# Connectors.net
KiCad netlist of a schematic drawn in Altium Designer
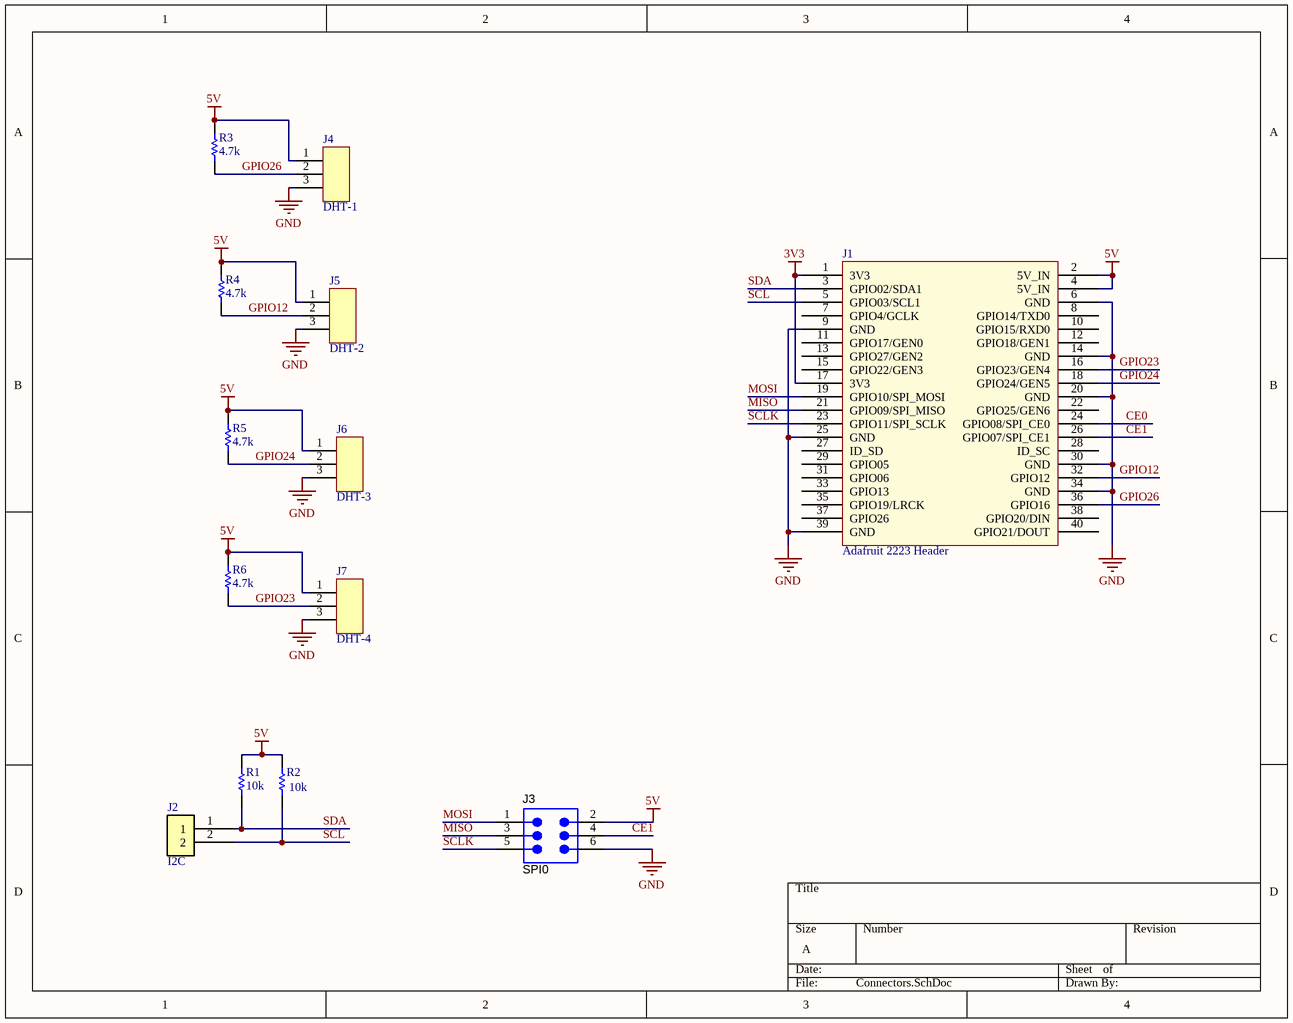
[diagram p0: Connectors.SchDoc]

(export (version "E")
  (design (tool "Eeschema 10.0.6"))
  (components
    (comp (ref "J1")
      (value "Adafruit 2223 Header")
      (footprint "PCB-dv9vmhrfa2chsb9gidwm-1")
      (description "GPIO Stacking Header for Pi A+/B+/Pi 2/Pi 3 - Extra-long 2x20 Pins")
      (libsource (lib "CommunityVault") (part "SYM-cbcb01f7cb9b140c-1"))
    )
    (comp (ref "J2")
      (value "I2C")
      (footprint "PCB-t2j72m1yraok0w090vy8-1")
      (description "Board-To-Board Connector, Right Angle, WR-PHD Series, Through Hole, Header, 2, 2.54 mm")
      (fields (field (name "MANUFACTURER PART NUMBER") "61300211021"))
      (libsource (lib "CommunityVault") (part "SYM-7939b1c60980a6fe-1"))
    )
    (comp (ref "J3")
      (value "SPI0")
      (footprint "PCB-195qa83xwzmdfln5hnix-1")
      (description "Board-To-Board Connector, WR-PHD Series, Surface Mount, Header, 6, 2.54 mm, Gold Plated Contacts")
      (fields (field (name "MANUFACTURER PART NUMBER") "61000621121"))
      (libsource (lib "CommunityVault") (part "Header_3x2"))
    )
    (comp (ref "J4")
      (value "DHT-1")
      (footprint "PCB-s0hfil65plaomi4ibvcw-1")
      (description "THT Vertical Pin Header WR-PHD, Pitch 2.54 mm, Single Row, 3 pins")
      (fields (field (name "MANUFACTURER PART NUMBER") "61300311121"))
      (libsource (lib "CommunityVault") (part "SYM-8a90426ffa175557-17"))
    )
    (comp (ref "J5")
      (value "DHT-2")
      (footprint "PCB-s0hfil65plaomi4ibvcw-1")
      (description "THT Vertical Pin Header WR-PHD, Pitch 2.54 mm, Single Row, 3 pins")
      (fields (field (name "MANUFACTURER PART NUMBER") "61300311121"))
      (libsource (lib "CommunityVault") (part "SYM-8a90426ffa175557-17"))
    )
    (comp (ref "J6")
      (value "DHT-3")
      (footprint "PCB-s0hfil65plaomi4ibvcw-1")
      (description "THT Vertical Pin Header WR-PHD, Pitch 2.54 mm, Single Row, 3 pins")
      (fields (field (name "MANUFACTURER PART NUMBER") "61300311121"))
      (libsource (lib "CommunityVault") (part "SYM-8a90426ffa175557-17"))
    )
    (comp (ref "J7")
      (value "DHT-4")
      (footprint "PCB-s0hfil65plaomi4ibvcw-1")
      (description "THT Vertical Pin Header WR-PHD, Pitch 2.54 mm, Single Row, 3 pins")
      (fields (field (name "MANUFACTURER PART NUMBER") "61300311121"))
      (libsource (lib "CommunityVault") (part "SYM-8a90426ffa175557-17"))
    )
    (comp (ref "R1")
      (value "10k")
      (footprint "PCB-urbe6pl2f36u5sj9z9e0-1")
      (description "Res, AEC-Q200, Thick Film, 10K, 5%, 0603")
      (fields (field (name "MANUFACTURER PART NUMBER") "CRGCQ0603J10K"))
      (libsource (lib "CommunityVault") (part "SYM-1974d512ef63c6b3-1"))
    )
    (comp (ref "R2")
      (value "10k")
      (footprint "PCB-urbe6pl2f36u5sj9z9e0-1")
      (description "Res, AEC-Q200, Thick Film, 10K, 5%, 0603")
      (fields (field (name "MANUFACTURER PART NUMBER") "CRGCQ0603J10K"))
      (libsource (lib "CommunityVault") (part "SYM-1974d512ef63c6b3-1"))
    )
    (comp (ref "R3")
      (value "4.7k")
      (footprint "PCB-etsube69rmkcafwxmreb-1")
      (description "Res Thin Film 0603 4.7K Ohm 1% 1/10W ±50ppm/°C Molded SMD SMD Paper T/R")
      (fields (field (name "MANUFACTURER PART NUMBER") "MCT06030C4701FP500"))
      (libsource (lib "CommunityVault") (part "SYM-e8892324e857374e-1"))
    )
    (comp (ref "R4")
      (value "4.7k")
      (footprint "PCB-etsube69rmkcafwxmreb-1")
      (description "Res Thin Film 0603 4.7K Ohm 1% 1/10W ±50ppm/°C Molded SMD SMD Paper T/R")
      (fields (field (name "MANUFACTURER PART NUMBER") "MCT06030C4701FP500"))
      (libsource (lib "CommunityVault") (part "SYM-e8892324e857374e-1"))
    )
    (comp (ref "R5")
      (value "4.7k")
      (footprint "PCB-etsube69rmkcafwxmreb-1")
      (description "Res Thin Film 0603 4.7K Ohm 1% 1/10W ±50ppm/°C Molded SMD SMD Paper T/R")
      (fields (field (name "MANUFACTURER PART NUMBER") "MCT06030C4701FP500"))
      (libsource (lib "CommunityVault") (part "SYM-e8892324e857374e-1"))
    )
    (comp (ref "R6")
      (value "4.7k")
      (footprint "PCB-etsube69rmkcafwxmreb-1")
      (description "Res Thin Film 0603 4.7K Ohm 1% 1/10W ±50ppm/°C Molded SMD SMD Paper T/R")
      (fields (field (name "MANUFACTURER PART NUMBER") "MCT06030C4701FP500"))
      (libsource (lib "CommunityVault") (part "SYM-e8892324e857374e-1"))
    )
  )
  (nets
    (net (code "1") (name "/CE0") (class "Default")
      (node (ref "J1") (pin "24") (pinfunction "GPIO08/SPI_CE0_24") (pintype "passive"))
    )
    (net (code "2") (name "/CE1") (class "Default")
      (node (ref "J1") (pin "26") (pinfunction "GPIO07/SPI_CE1_26") (pintype "passive"))
      (node (ref "J3") (pin "4") (pinfunction "4_4") (pintype "passive"))
    )
    (net (code "3") (name "/GPIO12") (class "Default")
      (node (ref "J1") (pin "32") (pinfunction "GPIO12_32") (pintype "passive"))
      (node (ref "J5") (pin "2") (pinfunction "2_2") (pintype "passive"))
      (node (ref "R4") (pin "1") (pinfunction "1_1") (pintype "passive"))
    )
    (net (code "4") (name "/GPIO23") (class "Default")
      (node (ref "J1") (pin "16") (pinfunction "GPIO23/GEN4_16") (pintype "passive"))
      (node (ref "J7") (pin "2") (pinfunction "2_2") (pintype "passive"))
      (node (ref "R6") (pin "1") (pinfunction "1_1") (pintype "passive"))
    )
    (net (code "5") (name "/GPIO24") (class "Default")
      (node (ref "J1") (pin "18") (pinfunction "GPIO24/GEN5_18") (pintype "passive"))
      (node (ref "J6") (pin "2") (pinfunction "2_2") (pintype "passive"))
      (node (ref "R5") (pin "1") (pinfunction "1_1") (pintype "passive"))
    )
    (net (code "6") (name "/GPIO26") (class "Default")
      (node (ref "J1") (pin "36") (pinfunction "GPIO16_36") (pintype "passive"))
      (node (ref "J4") (pin "2") (pinfunction "2_2") (pintype "passive"))
      (node (ref "R3") (pin "1") (pinfunction "1_1") (pintype "passive"))
    )
    (net (code "7") (name "/MISO") (class "Default")
      (node (ref "J1") (pin "21") (pinfunction "GPIO09/SPI_MISO_21") (pintype "passive"))
      (node (ref "J3") (pin "3") (pinfunction "3_3") (pintype "passive"))
    )
    (net (code "8") (name "/MOSI") (class "Default")
      (node (ref "J1") (pin "19") (pinfunction "GPIO10/SPI_MOSI_19") (pintype "passive"))
      (node (ref "J3") (pin "1") (pinfunction "1_1") (pintype "passive"))
    )
    (net (code "9") (name "/SCL") (class "Default")
      (node (ref "J1") (pin "5") (pinfunction "GPIO03/SCL1_5") (pintype "passive"))
      (node (ref "J2") (pin "2") (pinfunction "2_2") (pintype "passive"))
      (node (ref "R2") (pin "1") (pinfunction "1_1") (pintype "passive"))
    )
    (net (code "10") (name "/SCLK") (class "Default")
      (node (ref "J1") (pin "23") (pinfunction "GPIO11/SPI_SCLK_23") (pintype "passive"))
      (node (ref "J3") (pin "5") (pinfunction "5_5") (pintype "passive"))
    )
    (net (code "11") (name "/SDA") (class "Default")
      (node (ref "J1") (pin "3") (pinfunction "GPIO02/SDA1_3") (pintype "passive"))
      (node (ref "J2") (pin "1") (pinfunction "1_1") (pintype "passive"))
      (node (ref "R1") (pin "1") (pinfunction "1_1") (pintype "passive"))
    )
    (net (code "12") (name "3V3") (class "Default")
      (node (ref "J1") (pin "1") (pinfunction "3V3_1") (pintype "passive"))
      (node (ref "J1") (pin "17") (pinfunction "3V3_17") (pintype "passive"))
    )
    (net (code "13") (name "5V") (class "Default")
      (node (ref "J1") (pin "2") (pinfunction "5V_IN_2") (pintype "passive"))
      (node (ref "J1") (pin "4") (pinfunction "5V_IN_4") (pintype "passive"))
      (node (ref "J3") (pin "2") (pinfunction "2_2") (pintype "passive"))
      (node (ref "J4") (pin "1") (pinfunction "1_1") (pintype "passive"))
      (node (ref "J5") (pin "1") (pinfunction "1_1") (pintype "passive"))
      (node (ref "J6") (pin "1") (pinfunction "1_1") (pintype "passive"))
      (node (ref "J7") (pin "1") (pinfunction "1_1") (pintype "passive"))
      (node (ref "R1") (pin "2") (pinfunction "2_2") (pintype "passive"))
      (node (ref "R2") (pin "2") (pinfunction "2_2") (pintype "passive"))
      (node (ref "R3") (pin "2") (pinfunction "2_2") (pintype "passive"))
      (node (ref "R4") (pin "2") (pinfunction "2_2") (pintype "passive"))
      (node (ref "R5") (pin "2") (pinfunction "2_2") (pintype "passive"))
      (node (ref "R6") (pin "2") (pinfunction "2_2") (pintype "passive"))
    )
    (net (code "14") (name "GND") (class "Default")
      (node (ref "J1") (pin "14") (pinfunction "GND_14") (pintype "passive"))
      (node (ref "J1") (pin "20") (pinfunction "GND_20") (pintype "passive"))
      (node (ref "J1") (pin "25") (pinfunction "GND_25") (pintype "passive"))
      (node (ref "J1") (pin "30") (pinfunction "GND_30") (pintype "passive"))
      (node (ref "J1") (pin "34") (pinfunction "GND_34") (pintype "passive"))
      (node (ref "J1") (pin "39") (pinfunction "GND_39") (pintype "passive"))
      (node (ref "J1") (pin "6") (pinfunction "GND_6") (pintype "passive"))
      (node (ref "J1") (pin "9") (pinfunction "GND_9") (pintype "passive"))
      (node (ref "J3") (pin "6") (pinfunction "6_6") (pintype "passive"))
      (node (ref "J4") (pin "3") (pinfunction "3_3") (pintype "passive"))
      (node (ref "J5") (pin "3") (pinfunction "3_3") (pintype "passive"))
      (node (ref "J6") (pin "3") (pinfunction "3_3") (pintype "passive"))
      (node (ref "J7") (pin "3") (pinfunction "3_3") (pintype "passive"))
    )
    (net (code "15") (name "unconnected-(J1-GPIO4{slash}GCLK-Pad7)") (class "Default")
      (node (ref "J1") (pin "7") (pinfunction "GPIO4/GCLK_7") (pintype "passive"))
    )
    (net (code "16") (name "unconnected-(J1-GPIO05-Pad29)") (class "Default")
      (node (ref "J1") (pin "29") (pinfunction "GPIO05_29") (pintype "passive"))
    )
    (net (code "17") (name "unconnected-(J1-GPIO06-Pad31)") (class "Default")
      (node (ref "J1") (pin "31") (pinfunction "GPIO06_31") (pintype "passive"))
    )
    (net (code "18") (name "unconnected-(J1-GPIO13-Pad33)") (class "Default")
      (node (ref "J1") (pin "33") (pinfunction "GPIO13_33") (pintype "passive"))
    )
    (net (code "19") (name "unconnected-(J1-GPIO14{slash}TXD0-Pad8)") (class "Default")
      (node (ref "J1") (pin "8") (pinfunction "GPIO14/TXD0_8") (pintype "passive"))
    )
    (net (code "20") (name "unconnected-(J1-GPIO15{slash}RXD0-Pad10)") (class "Default")
      (node (ref "J1") (pin "10") (pinfunction "GPIO15/RXD0_10") (pintype "passive"))
    )
    (net (code "21") (name "unconnected-(J1-GPIO17{slash}GEN0-Pad11)") (class "Default")
      (node (ref "J1") (pin "11") (pinfunction "GPIO17/GEN0_11") (pintype "passive"))
    )
    (net (code "22") (name "unconnected-(J1-GPIO18{slash}GEN1-Pad12)") (class "Default")
      (node (ref "J1") (pin "12") (pinfunction "GPIO18/GEN1_12") (pintype "passive"))
    )
    (net (code "23") (name "unconnected-(J1-GPIO19{slash}LRCK-Pad35)") (class "Default")
      (node (ref "J1") (pin "35") (pinfunction "GPIO19/LRCK_35") (pintype "passive"))
    )
    (net (code "24") (name "unconnected-(J1-GPIO20{slash}DIN-Pad38)") (class "Default")
      (node (ref "J1") (pin "38") (pinfunction "GPIO20/DIN_38") (pintype "passive"))
    )
    (net (code "25") (name "unconnected-(J1-GPIO21{slash}DOUT-Pad40)") (class "Default")
      (node (ref "J1") (pin "40") (pinfunction "GPIO21/DOUT_40") (pintype "passive"))
    )
    (net (code "26") (name "unconnected-(J1-GPIO22{slash}GEN3-Pad15)") (class "Default")
      (node (ref "J1") (pin "15") (pinfunction "GPIO22/GEN3_15") (pintype "passive"))
    )
    (net (code "27") (name "unconnected-(J1-GPIO25{slash}GEN6-Pad22)") (class "Default")
      (node (ref "J1") (pin "22") (pinfunction "GPIO25/GEN6_22") (pintype "passive"))
    )
    (net (code "28") (name "unconnected-(J1-GPIO26-Pad37)") (class "Default")
      (node (ref "J1") (pin "37") (pinfunction "GPIO26_37") (pintype "passive"))
    )
    (net (code "29") (name "unconnected-(J1-GPIO27{slash}GEN2-Pad13)") (class "Default")
      (node (ref "J1") (pin "13") (pinfunction "GPIO27/GEN2_13") (pintype "passive"))
    )
    (net (code "30") (name "unconnected-(J1-ID_SC-Pad28)") (class "Default")
      (node (ref "J1") (pin "28") (pinfunction "ID_SC_28") (pintype "passive"))
    )
    (net (code "31") (name "unconnected-(J1-ID_SD-Pad27)") (class "Default")
      (node (ref "J1") (pin "27") (pinfunction "ID_SD_27") (pintype "passive"))
    )
  )
)
